# Touchstone.net
KiCad netlist of a schematic drawn in EAGLE
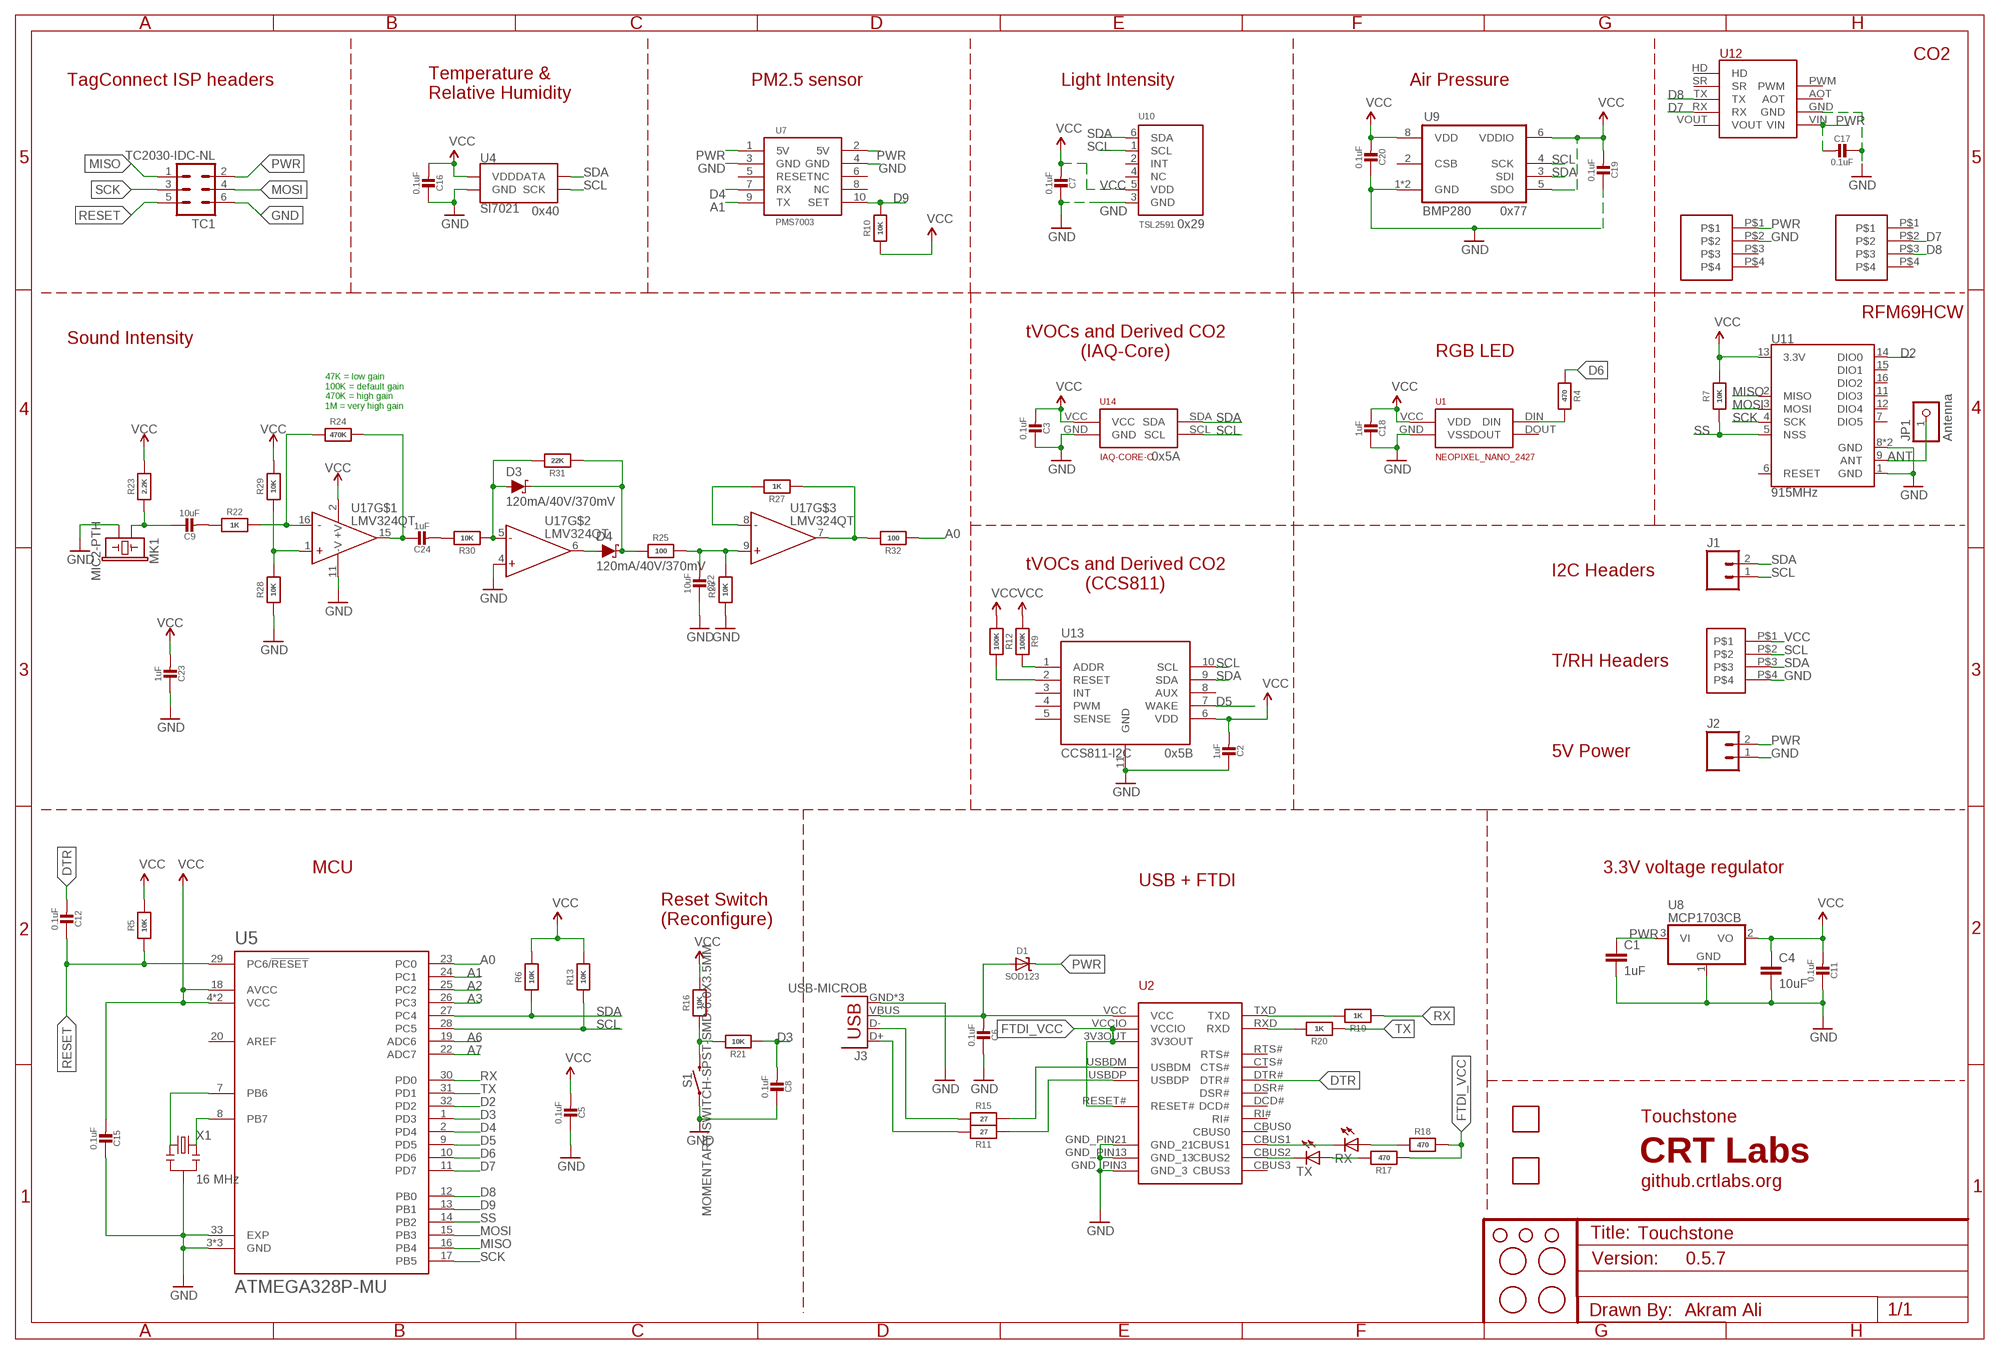
[diagram p0: schematic, sheet 1]

(export (version "E")
  (design (tool "Eeschema 10.0.6"))
  (components
    (comp (ref "C1")
      (value "1uF")
      (footprint "eagle-import:0805")
      (fields (field (name "MPN") "CC0805ZRY5V8BB105"))
      (libsource (lib "eagle-import") (part "CAP0805"))
    )
    (comp (ref "C2")
      (value "1uF")
      (footprint "eagle-import:MICROBUILDER__0402MP")
      (fields (field (name "MPN") "CC0402KRX5R6BB105"))
      (libsource (lib "eagle-import") (part "MICROBUILDER_CAP_CERAMIC_0402MP"))
    )
    (comp (ref "C3")
      (value "0.1uF")
      (footprint "eagle-import:MICROBUILDER__0402MP")
      (fields (field (name "MPN") "GRM155R71C104KA88J"))
      (libsource (lib "eagle-import") (part "MICROBUILDER_CAP_CERAMIC_0402MP"))
    )
    (comp (ref "C4")
      (value "10uF")
      (footprint "eagle-import:0805")
      (fields (field (name "MPN") "CC0805KKX5R6BB106"))
      (libsource (lib "eagle-import") (part "CAP0805"))
    )
    (comp (ref "C5")
      (value "0.1uF")
      (footprint "eagle-import:MICROBUILDER__0402MP")
      (fields (field (name "MPN") "GRM155R71C104KA88J"))
      (libsource (lib "eagle-import") (part "MICROBUILDER_CAP_CERAMIC_0402MP"))
    )
    (comp (ref "C6")
      (value "0.1uF")
      (footprint "eagle-import:MICROBUILDER__0402MP")
      (fields (field (name "MPN") "GRM155R71C104KA88J"))
      (libsource (lib "eagle-import") (part "MICROBUILDER_CAP_CERAMIC_0402MP"))
    )
    (comp (ref "C7")
      (value "0.1uF")
      (footprint "eagle-import:MICROBUILDER__0402MP")
      (fields (field (name "MPN") "GRM155R71C104KA88J"))
      (libsource (lib "eagle-import") (part "MICROBUILDER_CAP_CERAMIC_0402MP"))
    )
    (comp (ref "C8")
      (value "0.1uF")
      (footprint "eagle-import:MICROBUILDER__0402MP")
      (fields (field (name "MPN") "GRM155R71C104KA88J"))
      (libsource (lib "eagle-import") (part "MICROBUILDER_CAP_CERAMIC_0402MP"))
    )
    (comp (ref "C9")
      (value "10uF")
      (footprint "eagle-import:MICROBUILDER__0402MP")
      (fields (field (name "MPN") "GRJ155R60J106ME11D"))
      (libsource (lib "eagle-import") (part "MICROBUILDER_CAP_CERAMIC_0402MP"))
    )
    (comp (ref "C11")
      (value "0.1uF")
      (footprint "eagle-import:MICROBUILDER__0402MP")
      (fields (field (name "MPN") "GRM155R71C104KA88J"))
      (libsource (lib "eagle-import") (part "MICROBUILDER_CAP_CERAMIC_0402MP"))
    )
    (comp (ref "C12")
      (value "0.1uF")
      (footprint "eagle-import:MICROBUILDER__0402MP")
      (fields (field (name "MPN") "GRM155R71C104KA88J"))
      (libsource (lib "eagle-import") (part "MICROBUILDER_CAP_CERAMIC_0402MP"))
    )
    (comp (ref "C15")
      (value "0.1uF")
      (footprint "eagle-import:MICROBUILDER__0402MP")
      (fields (field (name "MPN") "GRM155R71C104KA88J"))
      (libsource (lib "eagle-import") (part "MICROBUILDER_CAP_CERAMIC_0402MP"))
    )
    (comp (ref "C16")
      (value "0.1uF")
      (footprint "eagle-import:MICROBUILDER__0402MP")
      (fields (field (name "MPN") "GRM155R71C104KA88J"))
      (libsource (lib "eagle-import") (part "MICROBUILDER_CAP_CERAMIC_0402MP"))
    )
    (comp (ref "C17")
      (value "0.1uF")
      (footprint "eagle-import:MICROBUILDER__0402MP")
      (fields (field (name "MPN") "GRM155R71C104KA88J"))
      (libsource (lib "eagle-import") (part "MICROBUILDER_CAP_CERAMIC_0402MP"))
    )
    (comp (ref "C18")
      (value "1uF")
      (footprint "eagle-import:MICROBUILDER__0402MP")
      (fields (field (name "MPN") "CC0402KRX5R6BB105"))
      (libsource (lib "eagle-import") (part "MICROBUILDER_CAP_CERAMIC_0402MP"))
    )
    (comp (ref "C19")
      (value "0.1uF")
      (footprint "eagle-import:MICROBUILDER__0402MP")
      (fields (field (name "MPN") "GRM155R71C104KA88J"))
      (libsource (lib "eagle-import") (part "MICROBUILDER_CAP_CERAMIC_0402MP"))
    )
    (comp (ref "C20")
      (value "0.1uF")
      (footprint "eagle-import:MICROBUILDER__0402MP")
      (fields (field (name "MPN") "GRM155R71C104KA88J"))
      (libsource (lib "eagle-import") (part "MICROBUILDER_CAP_CERAMIC_0402MP"))
    )
    (comp (ref "C22")
      (value "10uF")
      (footprint "eagle-import:MICROBUILDER__0402MP")
      (fields (field (name "MPN") "GRJ155R60J106ME11D"))
      (libsource (lib "eagle-import") (part "MICROBUILDER_CAP_CERAMIC_0402MP"))
    )
    (comp (ref "C23")
      (value "1uF")
      (footprint "eagle-import:MICROBUILDER__0402MP")
      (fields (field (name "MPN") "CC0402KRX5R6BB105"))
      (libsource (lib "eagle-import") (part "MICROBUILDER_CAP_CERAMIC_0402MP"))
    )
    (comp (ref "C24")
      (value "1uF")
      (footprint "eagle-import:MICROBUILDER__0402MP")
      (fields (field (name "MPN") "CC0402KRX5R6BB105"))
      (libsource (lib "eagle-import") (part "MICROBUILDER_CAP_CERAMIC_0402MP"))
    )
    (comp (ref "D1")
      (value "SOD123")
      (footprint "eagle-import:MICROBUILDER_SOD-123")
      (fields (field (name "MPN") "SD103AW-13-F"))
      (libsource (lib "eagle-import") (part "MICROBUILDER_DIODE-SCHOTTKYSOD-123"))
    )
    (comp (ref "D3")
      (value "120mA/40V/370mV")
      (footprint "eagle-import:SOD-523")
      (fields (field (name "MPN") "RB751S40T1G"))
      (libsource (lib "eagle-import") (part "DIODE-SCHOTTKY-RB751S40"))
    )
    (comp (ref "D4")
      (value "120mA/40V/370mV")
      (footprint "eagle-import:SOD-523")
      (fields (field (name "MPN") "RB751S40T1G"))
      (libsource (lib "eagle-import") (part "DIODE-SCHOTTKY-RB751S40"))
    )
    (comp (ref "H1")
      (value "STAND-OFF")
      (footprint "eagle-import:STAND-OFF")
      (libsource (lib "eagle-import") (part "STAND-OFF"))
    )
    (comp (ref "H2")
      (value "STAND-OFF")
      (footprint "eagle-import:STAND-OFF")
      (libsource (lib "eagle-import") (part "STAND-OFF"))
    )
    (comp (ref "H3")
      (value "STAND-OFF")
      (footprint "eagle-import:STAND-OFF")
      (libsource (lib "eagle-import") (part "STAND-OFF"))
    )
    (comp (ref "J1")
      (value "M02PTH")
      (footprint "eagle-import:1X02")
      (libsource (lib "eagle-import") (part "M02PTH"))
    )
    (comp (ref "J2")
      (value "M02PTH")
      (footprint "eagle-import:1X02")
      (libsource (lib "eagle-import") (part "M02PTH"))
    )
    (comp (ref "J3")
      (value "USB-MICROB")
      (footprint "eagle-import:USB-MICROB")
      (fields (field (name "MPN") "ZX62-B-5PA(33)"))
      (libsource (lib "eagle-import") (part "USB-MICROB"))
    )
    (comp (ref "JP1")
      (value "Antenna")
      (footprint "eagle-import:1X01-CLEANBIG")
      (fields (field (name "MPN") "Helical antenna"))
      (libsource (lib "eagle-import") (part "PINHD-1X1CB"))
    )
    (comp (ref "MK1")
      (value "MIC2-PTH")
      (footprint "eagle-import:MICROPHONE-PTH-4.0MM")
      (fields (field (name "MPN") "TOM-1545P-R"))
      (libsource (lib "eagle-import") (part "MIC2-PTH"))
    )
    (comp (ref "R4")
      (value "470")
      (footprint "eagle-import:MICROBUILDER__0402MP")
      (fields (field (name "MPN") "RC0402JR-07470RL"))
      (libsource (lib "eagle-import") (part "MICROBUILDER_RESISTOR_0402MP"))
    )
    (comp (ref "R5")
      (value "10K")
      (footprint "eagle-import:MICROBUILDER__0402MP")
      (fields (field (name "MPN") "RC0402JR-0710KL"))
      (libsource (lib "eagle-import") (part "MICROBUILDER_RESISTOR_0402MP"))
    )
    (comp (ref "R6")
      (value "10K")
      (footprint "eagle-import:MICROBUILDER__0402MP")
      (fields (field (name "MPN") "RC0402JR-0710KL"))
      (libsource (lib "eagle-import") (part "MICROBUILDER_RESISTOR_0402MP"))
    )
    (comp (ref "R7")
      (value "10K")
      (footprint "eagle-import:MICROBUILDER__0402MP")
      (fields (field (name "MPN") "RC0402JR-0710KL"))
      (libsource (lib "eagle-import") (part "MICROBUILDER_RESISTOR_0402MP"))
    )
    (comp (ref "R9")
      (value "100K")
      (footprint "eagle-import:MICROBUILDER__0402MP")
      (fields (field (name "MPN") "RC0402FR-07100KL"))
      (libsource (lib "eagle-import") (part "MICROBUILDER_RESISTOR_0402MP"))
    )
    (comp (ref "R10")
      (value "10K")
      (footprint "eagle-import:MICROBUILDER__0402MP")
      (fields (field (name "MPN") "RC0402JR-0710KL"))
      (libsource (lib "eagle-import") (part "MICROBUILDER_RESISTOR_0402MP"))
    )
    (comp (ref "R11")
      (value "27")
      (footprint "eagle-import:MICROBUILDER__0402MP")
      (fields (field (name "MPN") "RC0402JR-0727RL"))
      (libsource (lib "eagle-import") (part "MICROBUILDER_RESISTOR_0402MP"))
    )
    (comp (ref "R12")
      (value "100K")
      (footprint "eagle-import:MICROBUILDER__0402MP")
      (fields (field (name "MPN") "RC0402FR-07100KL"))
      (libsource (lib "eagle-import") (part "MICROBUILDER_RESISTOR_0402MP"))
    )
    (comp (ref "R13")
      (value "10K")
      (footprint "eagle-import:MICROBUILDER__0402MP")
      (fields (field (name "MPN") "RC0402JR-0710KL"))
      (libsource (lib "eagle-import") (part "MICROBUILDER_RESISTOR_0402MP"))
    )
    (comp (ref "R15")
      (value "27")
      (footprint "eagle-import:MICROBUILDER__0402MP")
      (fields (field (name "MPN") "RC0402JR-0727RL"))
      (libsource (lib "eagle-import") (part "MICROBUILDER_RESISTOR_0402MP"))
    )
    (comp (ref "R16")
      (value "10K")
      (footprint "eagle-import:MICROBUILDER__0402MP")
      (fields (field (name "MPN") "RC0402JR-0710KL"))
      (libsource (lib "eagle-import") (part "MICROBUILDER_RESISTOR_0402MP"))
    )
    (comp (ref "R17")
      (value "470")
      (footprint "eagle-import:MICROBUILDER__0402MP")
      (fields (field (name "MPN") "RC0402JR-07470RL"))
      (libsource (lib "eagle-import") (part "MICROBUILDER_RESISTOR_0402MP"))
    )
    (comp (ref "R18")
      (value "470")
      (footprint "eagle-import:MICROBUILDER__0402MP")
      (fields (field (name "MPN") "RC0402JR-07470RL"))
      (libsource (lib "eagle-import") (part "MICROBUILDER_RESISTOR_0402MP"))
    )
    (comp (ref "R19")
      (value "1K")
      (footprint "eagle-import:MICROBUILDER__0402MP")
      (fields (field (name "MPN") "RC0402JR-071KL"))
      (libsource (lib "eagle-import") (part "MICROBUILDER_RESISTOR_0402MP"))
    )
    (comp (ref "R20")
      (value "1K")
      (footprint "eagle-import:MICROBUILDER__0402MP")
      (fields (field (name "MPN") "RC0402JR-071KL"))
      (libsource (lib "eagle-import") (part "MICROBUILDER_RESISTOR_0402MP"))
    )
    (comp (ref "R21")
      (value "10K")
      (footprint "eagle-import:MICROBUILDER__0402MP")
      (fields (field (name "MPN") "RC0402JR-0710KL"))
      (libsource (lib "eagle-import") (part "MICROBUILDER_RESISTOR_0402MP"))
    )
    (comp (ref "R22")
      (value "1K")
      (footprint "eagle-import:MICROBUILDER__0402MP")
      (fields (field (name "MPN") "RC0402JR-071KL"))
      (libsource (lib "eagle-import") (part "Adafruit PowerBoost 1000C Rev B_MICROBUILDER_RESISTOR_0402MP"))
    )
    (comp (ref "R23")
      (value "2.2K")
      (footprint "eagle-import:MICROBUILDER__0402MP")
      (fields (field (name "MPN") "RC0402FR-072K2L"))
      (libsource (lib "eagle-import") (part "Adafruit PowerBoost 1000C Rev B_MICROBUILDER_RESISTOR_0402MP"))
    )
    (comp (ref "R24")
      (value "470K")
      (footprint "eagle-import:MICROBUILDER__0402MP")
      (fields (field (name "MPN") "RC0402FR-071ML"))
      (libsource (lib "eagle-import") (part "Adafruit PowerBoost 1000C Rev B_MICROBUILDER_RESISTOR_0402MP"))
    )
    (comp (ref "R25")
      (value "100")
      (footprint "eagle-import:MICROBUILDER__0402MP")
      (fields (field (name "MPN") "RC0402FR-07100RL"))
      (libsource (lib "eagle-import") (part "Adafruit PowerBoost 1000C Rev B_MICROBUILDER_RESISTOR_0402MP"))
    )
    (comp (ref "R26")
      (value "10K")
      (footprint "eagle-import:MICROBUILDER__0402MP")
      (fields (field (name "MPN") "RC0402JR-0710KL"))
      (libsource (lib "eagle-import") (part "Adafruit PowerBoost 1000C Rev B_MICROBUILDER_RESISTOR_0402MP"))
    )
    (comp (ref "R27")
      (value "1K")
      (footprint "eagle-import:MICROBUILDER__0402MP")
      (fields (field (name "MPN") "RC0402JR-071KL"))
      (libsource (lib "eagle-import") (part "Adafruit PowerBoost 1000C Rev B_MICROBUILDER_RESISTOR_0402MP"))
    )
    (comp (ref "R28")
      (value "10K")
      (footprint "eagle-import:MICROBUILDER__0402MP")
      (fields (field (name "MPN") "RC0402JR-0710KL"))
      (libsource (lib "eagle-import") (part "Adafruit PowerBoost 1000C Rev B_MICROBUILDER_RESISTOR_0402MP"))
    )
    (comp (ref "R29")
      (value "10K")
      (footprint "eagle-import:MICROBUILDER__0402MP")
      (fields (field (name "MPN") "RC0402JR-0710KL"))
      (libsource (lib "eagle-import") (part "Adafruit PowerBoost 1000C Rev B_MICROBUILDER_RESISTOR_0402MP"))
    )
    (comp (ref "R30")
      (value "10K")
      (footprint "eagle-import:MICROBUILDER__0402MP")
      (fields (field (name "MPN") "RC0402JR-0710KL"))
      (libsource (lib "eagle-import") (part "Adafruit PowerBoost 1000C Rev B_MICROBUILDER_RESISTOR_0402MP"))
    )
    (comp (ref "R31")
      (value "22K")
      (footprint "eagle-import:MICROBUILDER__0402MP")
      (fields (field (name "MPN") "RC0402JR-0722KL"))
      (libsource (lib "eagle-import") (part "Adafruit PowerBoost 1000C Rev B_MICROBUILDER_RESISTOR_0402MP"))
    )
    (comp (ref "R32")
      (value "100")
      (footprint "eagle-import:MICROBUILDER__0402MP")
      (fields (field (name "MPN") "RC0402FR-07100RL"))
      (libsource (lib "eagle-import") (part "Adafruit PowerBoost 1000C Rev B_MICROBUILDER_RESISTOR_0402MP"))
    )
    (comp (ref "RX")
      (value "LEDCHIPLED_0805")
      (footprint "eagle-import:CHIPLED_0805")
      (fields (field (name "MPN") "LG R971-KN-1"))
      (libsource (lib "eagle-import") (part "LEDCHIPLED_0805"))
    )
    (comp (ref "S1")
      (value "MOMENTARY-SWITCH-SPST-SMD-6.0X3.5MM")
      (footprint "eagle-import:TACTILE_SWITCH_SMD_6.0X3.5MM")
      (fields (field (name "MPN") "RS-032G05A3-SM RT"))
      (libsource (lib "eagle-import") (part "MOMENTARY-SWITCH-SPST-SMD-6.0X3.5MM"))
    )
    (comp (ref "TC1")
      (value "TC2030-IDC-NL")
      (footprint "eagle-import:TC2030-IDC-NL")
      (libsource (lib "eagle-import") (part "TC2030-IDC-NL"))
    )
    (comp (ref "TX")
      (value "LEDCHIPLED_0805")
      (footprint "eagle-import:CHIPLED_0805")
      (fields (field (name "MPN") "LG R971-KN-1"))
      (libsource (lib "eagle-import") (part "LEDCHIPLED_0805"))
    )
    (comp (ref "U$1")
      (value "FIDUCIAL")
      (footprint "eagle-import:FIDUCIAL_1MM")
      (libsource (lib "eagle-import") (part "FIDUCIAL"))
    )
    (comp (ref "U$2")
      (value "FIDUCIAL")
      (footprint "eagle-import:FIDUCIAL_1MM")
      (libsource (lib "eagle-import") (part "FIDUCIAL"))
    )
    (comp (ref "U$3")
      (value "FIDUCIAL")
      (footprint "eagle-import:FIDUCIAL_1MM")
      (libsource (lib "eagle-import") (part "FIDUCIAL"))
    )
    (comp (ref "U$4")
      (value "0878980426")
      (footprint "eagle-import:CONN_4POS_VERT_2.54_SMD")
      (libsource (lib "eagle-import") (part "0878980426"))
    )
    (comp (ref "U$5")
      (value "0878980426")
      (footprint "eagle-import:CONN_4POS_VERT_2.54_SMD")
      (libsource (lib "eagle-import") (part "0878980426"))
    )
    (comp (ref "U$6")
      (value "CONN_HDR_1.27MM_SMD_4POS")
      (footprint "eagle-import:CONN_HDR_1.27MM_SMD_4POS")
      (fields (field (name "MPN") "M50-3630442"))
      (libsource (lib "eagle-import") (part "CONN_HDR_1.27MM_SMD_4POS"))
    )
    (comp (ref "U$7")
      (value "FIDUCIAL")
      (footprint "eagle-import:FIDUCIAL_1MM")
      (libsource (lib "eagle-import") (part "FIDUCIAL"))
    )
    (comp (ref "U1")
      (value "NEOPIXEL_NANO_2427")
      (footprint "eagle-import:SK6805-2427")
      (fields (field (name "MPN") "3484"))
      (libsource (lib "eagle-import") (part "NEOPIXEL_NANO_2427"))
    )
    (comp (ref "U2")
      (value "FT231XQ-R")
      (footprint "eagle-import:FTDI_FT231XQ-R_PACKAGE")
      (libsource (lib "eagle-import") (part "FT231XQ-R"))
    )
    (comp (ref "U4")
      (value "SI7021")
      (footprint "eagle-import:DFN-6-3X3-SI7021")
      (fields (field (name "MPN") "SI7021-A20-GM1"))
      (libsource (lib "eagle-import") (part "SI7021"))
    )
    (comp (ref "U5")
      (value "ATMEGA328P-MU")
      (footprint "eagle-import:QFN50P500X500X100-33N")
      (fields (field (name "MF") "Atmel"))
      (libsource (lib "eagle-import") (part "ATMEGA328P-MU"))
    )
    (comp (ref "U7")
      (value "PMS7003")
      (footprint "eagle-import:PMS7003_RECEPTACLE_1.27MM_2X5")
      (fields (field (name "MPN") "20021311-00012T4LF"))
      (libsource (lib "eagle-import") (part "PMS7003"))
    )
    (comp (ref "U8")
      (value "MCP1703CB")
      (footprint "eagle-import:SOT23")
      (fields (field (name "MPN") "MCP1703T-3302E/CB"))
      (libsource (lib "eagle-import") (part "MCP1703CB"))
    )
    (comp (ref "U9")
      (value "BMP280")
      (footprint "eagle-import:BMP280")
      (libsource (lib "eagle-import") (part "BMP280"))
    )
    (comp (ref "U10")
      (value "TSL2591")
      (footprint "eagle-import:DFN6_TAOS")
      (fields (field (name "MPN") "TSL25911FN "))
      (libsource (lib "eagle-import") (part "LIGHT_TSL2591"))
    )
    (comp (ref "U11")
      (value "915MHz")
      (footprint "eagle-import:RFM69HCW-XXXS2")
      (fields (field (name "MPN") "RFM69HCW"))
      (libsource (lib "eagle-import") (part "RFM69HCW-915"))
    )
    (comp (ref "U12")
      (value "MH-Z19")
      (footprint "eagle-import:MH-Z19")
      (fields (field (name "MPN") "MH-z19"))
      (libsource (lib "eagle-import") (part "MH-Z19"))
    )
    (comp (ref "U13")
      (value "CCS811-I2C")
      (footprint "eagle-import:LGA")
      (fields (field (name "MPN") "CCS811"))
      (libsource (lib "eagle-import") (part "CCS811-I2C"))
    )
    (comp (ref "U14")
      (value "IAQ-CORE-C")
      (footprint "eagle-import:IAQ-CORE-C")
      (libsource (lib "eagle-import") (part "IAQ-CORE-C"))
    )
    (comp (ref "U15")
      (value "VLP-450-F")
      (footprint "eagle-import:VLP-450-F")
      (fields (field (name "MPN") "VLP-650-F"))
      (libsource (lib "eagle-import") (part "VLP-450-F"))
    )
    (comp (ref "U16")
      (value "VLP-450-F")
      (footprint "eagle-import:VLP-450-F")
      (fields (field (name "MPN") "VLP-550-F"))
      (libsource (lib "eagle-import") (part "VLP-450-F"))
    )
    (comp (ref "U17")
      (value "LMV324QT")
      (footprint "eagle-import:QFN-16_3X3")
      (fields (field (name "MPN") "LM324QT"))
      (libsource (lib "eagle-import") (part "LMV324QT"))
    )
    (comp (ref "X1")
      (value "16 MHz")
      (footprint "eagle-import:RESONATOR-SMD")
      (fields (field (name "MPN") "CSTCE16M0V53-R0"))
      (libsource (lib "eagle-import") (part "RESONATORSMD"))
    )
  )
  (nets
    (net (code "1") (name "/A0") (class "Default")
      (node (ref "R32") (pin "1") (pinfunction "1_1") (pintype "passive"))
      (node (ref "U5") (pin "23") (pinfunction "PC0_23") (pintype "bidirectional"))
    )
    (net (code "2") (name "/A1") (class "Default")
      (node (ref "U5") (pin "24") (pinfunction "PC1_24") (pintype "bidirectional"))
      (node (ref "U7") (pin "9") (pinfunction "TX_9") (pintype "bidirectional"))
    )
    (net (code "3") (name "/A2") (class "Default")
      (node (ref "U5") (pin "25") (pinfunction "PC2_25") (pintype "bidirectional"))
    )
    (net (code "4") (name "/A3") (class "Default")
      (node (ref "U5") (pin "26") (pinfunction "PC3_26") (pintype "bidirectional"))
    )
    (net (code "5") (name "/A6") (class "Default")
      (node (ref "U5") (pin "19") (pinfunction "ADC6_19") (pintype "bidirectional"))
    )
    (net (code "6") (name "/A7") (class "Default")
      (node (ref "U5") (pin "22") (pinfunction "ADC7_22") (pintype "bidirectional"))
    )
    (net (code "7") (name "/ANT") (class "Default")
      (node (ref "JP1") (pin "1") (pinfunction "1_1") (pintype "passive"))
      (node (ref "U11") (pin "9") (pinfunction "ANT_9") (pintype "passive"))
    )
    (net (code "8") (name "/D2") (class "Default")
      (node (ref "U11") (pin "14") (pinfunction "DIO0_14") (pintype "bidirectional"))
      (node (ref "U5") (pin "32") (pinfunction "PD2_32") (pintype "bidirectional"))
    )
    (net (code "9") (name "/D3") (class "Default")
      (node (ref "C8") (pin "2") (pinfunction "2_2") (pintype "passive"))
      (node (ref "R21") (pin "1") (pinfunction "1_1") (pintype "passive"))
      (node (ref "U5") (pin "1") (pinfunction "PD3_1") (pintype "bidirectional"))
    )
    (net (code "10") (name "/D4") (class "Default")
      (node (ref "U5") (pin "2") (pinfunction "PD4_2") (pintype "bidirectional"))
      (node (ref "U7") (pin "7") (pinfunction "RX_7") (pintype "bidirectional"))
    )
    (net (code "11") (name "/D5") (class "Default")
      (node (ref "U13") (pin "7") (pinfunction "WAKE_7") (pintype "bidirectional"))
      (node (ref "U5") (pin "9") (pinfunction "PD5_9") (pintype "bidirectional"))
    )
    (net (code "12") (name "/D7") (class "Default")
      (node (ref "U$5") (pin "P$2") (pinfunction "P$2_P$2") (pintype "bidirectional"))
      (node (ref "U12") (pin "RX") (pinfunction "RX_RX") (pintype "bidirectional"))
      (node (ref "U5") (pin "11") (pinfunction "PD7_11") (pintype "bidirectional"))
    )
    (net (code "13") (name "/D8") (class "Default")
      (node (ref "U$5") (pin "P$3") (pinfunction "P$3_P$3") (pintype "bidirectional"))
      (node (ref "U12") (pin "TX") (pinfunction "TX_TX") (pintype "bidirectional"))
      (node (ref "U5") (pin "12") (pinfunction "PB0_12") (pintype "bidirectional"))
    )
    (net (code "14") (name "/D9") (class "Default")
      (node (ref "R10") (pin "2") (pinfunction "2_2") (pintype "passive"))
      (node (ref "U5") (pin "13") (pinfunction "PB1_13") (pintype "bidirectional"))
      (node (ref "U7") (pin "10") (pinfunction "SET_10") (pintype "bidirectional"))
    )
    (net (code "15") (name "/SCL") (class "Default")
      (node (ref "J1") (pin "1") (pinfunction "1_1") (pintype "passive"))
      (node (ref "R13") (pin "1") (pinfunction "1_1") (pintype "passive"))
      (node (ref "U$6") (pin "P$2") (pinfunction "P$2_P$2") (pintype "bidirectional"))
      (node (ref "U10") (pin "1") (pinfunction "SCL_1") (pintype "bidirectional"))
      (node (ref "U13") (pin "10") (pinfunction "SCL_10") (pintype "bidirectional"))
      (node (ref "U14") (pin "SCL") (pinfunction "SCL_SCL") (pintype "bidirectional"))
      (node (ref "U4") (pin "SCK") (pinfunction "SCK_SCK") (pintype "input"))
      (node (ref "U5") (pin "28") (pinfunction "PC5_28") (pintype "bidirectional"))
      (node (ref "U9") (pin "4") (pinfunction "SCK_4") (pintype "bidirectional"))
    )
    (net (code "16") (name "/SDA") (class "Default")
      (node (ref "J1") (pin "2") (pinfunction "2_2") (pintype "passive"))
      (node (ref "R6") (pin "1") (pinfunction "1_1") (pintype "passive"))
      (node (ref "U$6") (pin "P$3") (pinfunction "P$3_P$3") (pintype "bidirectional"))
      (node (ref "U10") (pin "6") (pinfunction "SDA_6") (pintype "bidirectional"))
      (node (ref "U13") (pin "9") (pinfunction "SDA_9") (pintype "bidirectional"))
      (node (ref "U14") (pin "SDA") (pinfunction "SDA_SDA") (pintype "bidirectional"))
      (node (ref "U4") (pin "DATA") (pinfunction "DATA_DATA") (pintype "bidirectional"))
      (node (ref "U5") (pin "27") (pinfunction "PC4_27") (pintype "bidirectional"))
      (node (ref "U9") (pin "3") (pinfunction "SDI_3") (pintype "bidirectional"))
    )
    (net (code "17") (name "/SS") (class "Default")
      (node (ref "R7") (pin "1") (pinfunction "1_1") (pintype "passive"))
      (node (ref "U11") (pin "5") (pinfunction "NSS_5") (pintype "input"))
      (node (ref "U5") (pin "14") (pinfunction "PB2_14") (pintype "bidirectional"))
    )
    (net (code "18") (name "D6") (class "Default")
      (node (ref "R4") (pin "1") (pinfunction "1_1") (pintype "passive"))
      (node (ref "U5") (pin "10") (pinfunction "PD6_10") (pintype "bidirectional"))
    )
    (net (code "19") (name "DTR") (class "Default")
      (node (ref "C12") (pin "2") (pinfunction "2_2") (pintype "passive"))
      (node (ref "U2") (pin "DTR#") (pinfunction "DTR#_DTR#") (pintype "bidirectional"))
    )
    (net (code "20") (name "FTDI_VCC") (class "Default")
      (node (ref "R17") (pin "1") (pinfunction "1_1") (pintype "passive"))
      (node (ref "R18") (pin "2") (pinfunction "2_2") (pintype "passive"))
      (node (ref "U2") (pin "3V3OUT") (pinfunction "3V3OUT_3V3OUT") (pintype "bidirectional"))
      (node (ref "U2") (pin "RESET#") (pinfunction "RESET#_RESET#") (pintype "bidirectional"))
      (node (ref "U2") (pin "VCCIO") (pinfunction "VCCIO_VCCIO") (pintype "bidirectional"))
    )
    (net (code "21") (name "GND") (class "Default")
      (node (ref "C1") (pin "2") (pinfunction "2_2") (pintype "passive"))
      (node (ref "C11") (pin "1") (pinfunction "1_1") (pintype "passive"))
      (node (ref "C15") (pin "1") (pinfunction "1_1") (pintype "passive"))
      (node (ref "C16") (pin "1") (pinfunction "1_1") (pintype "passive"))
      (node (ref "C17") (pin "1") (pinfunction "1_1") (pintype "passive"))
      (node (ref "C18") (pin "1") (pinfunction "1_1") (pintype "passive"))
      (node (ref "C19") (pin "1") (pinfunction "1_1") (pintype "passive"))
      (node (ref "C2") (pin "1") (pinfunction "1_1") (pintype "passive"))
      (node (ref "C20") (pin "1") (pinfunction "1_1") (pintype "passive"))
      (node (ref "C22") (pin "1") (pinfunction "1_1") (pintype "passive"))
      (node (ref "C23") (pin "1") (pinfunction "1_1") (pintype "passive"))
      (node (ref "C3") (pin "1") (pinfunction "1_1") (pintype "passive"))
      (node (ref "C4") (pin "2") (pinfunction "2_2") (pintype "passive"))
      (node (ref "C5") (pin "1") (pinfunction "1_1") (pintype "passive"))
      (node (ref "C6") (pin "1") (pinfunction "1_1") (pintype "passive"))
      (node (ref "C7") (pin "1") (pinfunction "1_1") (pintype "passive"))
      (node (ref "C8") (pin "1") (pinfunction "1_1") (pintype "passive"))
      (node (ref "J2") (pin "1") (pinfunction "1_1") (pintype "passive"))
      (node (ref "J3") (pin "GND") (pinfunction "GND_GND") (pintype "bidirectional"))
      (node (ref "J3") (pin "MT1") (pinfunction "GND_MT1") (pintype "bidirectional"))
      (node (ref "J3") (pin "MT2") (pinfunction "GND_MT2") (pintype "bidirectional"))
      (node (ref "MK1") (pin "GND") (pinfunction "2_GND") (pintype "passive"))
      (node (ref "R26") (pin "1") (pinfunction "1_1") (pintype "passive"))
      (node (ref "R28") (pin "1") (pinfunction "1_1") (pintype "passive"))
      (node (ref "S1") (pin "1") (pinfunction "1_1") (pintype "passive"))
      (node (ref "TC1") (pin "6") (pinfunction "6_6") (pintype "passive"))
      (node (ref "U$4") (pin "P$2") (pinfunction "P$2_P$2") (pintype "bidirectional"))
      (node (ref "U$6") (pin "P$4") (pinfunction "P$4_P$4") (pintype "bidirectional"))
      (node (ref "U1") (pin "GND") (pinfunction "VSS_GND") (pintype "bidirectional"))
      (node (ref "U10") (pin "3") (pinfunction "GND_3") (pintype "power_in"))
      (node (ref "U11") (pin "1") (pinfunction "GND_1") (pintype "power_in"))
      (node (ref "U11") (pin "10") (pinfunction "GND_10") (pintype "power_in"))
      (node (ref "U11") (pin "8") (pinfunction "GND_8") (pintype "power_in"))
      (node (ref "U12") (pin "GND") (pinfunction "GND_GND") (pintype "bidirectional"))
      (node (ref "U13") (pin "11") (pinfunction "GND_11") (pintype "bidirectional"))
      (node (ref "U14") (pin "GND") (pinfunction "GND_GND") (pintype "bidirectional"))
      (node (ref "U17") (pin "11") (pinfunction "-V_11") (pintype "power_in"))
      (node (ref "U17") (pin "4") (pinfunction "+IN_4") (pintype "input"))
      (node (ref "U2") (pin "GND_PIN13") (pinfunction "GND_13_GND_PIN13") (pintype "bidirectional"))
      (node (ref "U2") (pin "GND_PIN21") (pinfunction "GND_21_GND_PIN21") (pintype "bidirectional"))
      (node (ref "U2") (pin "GND_PIN3") (pinfunction "GND_3_GND_PIN3") (pintype "bidirectional"))
      (node (ref "U4") (pin "GND") (pinfunction "GND_GND") (pintype "power_in"))
      (node (ref "U5") (pin "21") (pinfunction "GND_21") (pintype "power_in"))
      (node (ref "U5") (pin "3") (pinfunction "GND_3") (pintype "power_in"))
      (node (ref "U5") (pin "33") (pinfunction "EXP_33") (pintype "power_in"))
      (node (ref "U5") (pin "5") (pinfunction "GND_5") (pintype "power_in"))
      (node (ref "U7") (pin "3") (pinfunction "GND_3") (pintype "bidirectional"))
      (node (ref "U7") (pin "4") (pinfunction "GND_4") (pintype "bidirectional"))
      (node (ref "U8") (pin "1") (pinfunction "GND_1") (pintype "passive"))
      (node (ref "U9") (pin "1") (pinfunction "GND_1") (pintype "power_in"))
      (node (ref "U9") (pin "7") (pinfunction "GND_7") (pintype "power_in"))
      (node (ref "X1") (pin "2") (pinfunction "2_2") (pintype "passive"))
    )
    (net (code "22") (name "MISO") (class "Default")
      (node (ref "TC1") (pin "1") (pinfunction "1_1") (pintype "passive"))
      (node (ref "U11") (pin "2") (pinfunction "MISO_2") (pintype "bidirectional"))
      (node (ref "U5") (pin "16") (pinfunction "PB4_16") (pintype "bidirectional"))
    )
    (net (code "23") (name "MOSI") (class "Default")
      (node (ref "TC1") (pin "4") (pinfunction "4_4") (pintype "passive"))
      (node (ref "U11") (pin "3") (pinfunction "MOSI_3") (pintype "input"))
      (node (ref "U5") (pin "15") (pinfunction "PB3_15") (pintype "bidirectional"))
    )
    (net (code "24") (name "Net-(C6-Pad2)") (class "Default")
      (node (ref "C6") (pin "2") (pinfunction "2_2") (pintype "passive"))
      (node (ref "D1") (pin "A") (pinfunction "A_A") (pintype "passive"))
      (node (ref "J3") (pin "VBUS") (pinfunction "VBUS_VBUS") (pintype "bidirectional"))
      (node (ref "U2") (pin "VCC") (pinfunction "VCC_VCC") (pintype "bidirectional"))
    )
    (net (code "25") (name "Net-(C9-Pad2)") (class "Default")
      (node (ref "C9") (pin "2") (pinfunction "2_2") (pintype "passive"))
      (node (ref "R22") (pin "1") (pinfunction "1_1") (pintype "passive"))
    )
    (net (code "26") (name "Net-(C24-Pad2)") (class "Default")
      (node (ref "C24") (pin "2") (pinfunction "2_2") (pintype "passive"))
      (node (ref "R30") (pin "2") (pinfunction "2_2") (pintype "passive"))
    )
    (net (code "27") (name "Net-(D3-PadC)") (class "Default")
      (node (ref "D3") (pin "C") (pinfunction "C_C") (pintype "passive"))
      (node (ref "D4") (pin "C") (pinfunction "C_C") (pintype "passive"))
      (node (ref "R25") (pin "1") (pinfunction "1_1") (pintype "passive"))
      (node (ref "R31") (pin "1") (pinfunction "1_1") (pintype "passive"))
    )
    (net (code "28") (name "Net-(J3-PadD+)") (class "Default")
      (node (ref "J3") (pin "D+") (pinfunction "D+_D+") (pintype "bidirectional"))
      (node (ref "R11") (pin "2") (pinfunction "2_2") (pintype "passive"))
    )
    (net (code "29") (name "Net-(J3-PadD-)") (class "Default")
      (node (ref "J3") (pin "D-") (pinfunction "D-_D-") (pintype "bidirectional"))
      (node (ref "R15") (pin "1") (pinfunction "1_1") (pintype "passive"))
    )
    (net (code "30") (name "Net-(MK1-1)") (class "Default")
      (node (ref "C9") (pin "1") (pinfunction "1_1") (pintype "passive"))
      (node (ref "MK1") (pin "OUT") (pinfunction "1_OUT") (pintype "passive"))
      (node (ref "R23") (pin "1") (pinfunction "1_1") (pintype "passive"))
    )
    (net (code "31") (name "Net-(R4-Pad2)") (class "Default")
      (node (ref "R4") (pin "2") (pinfunction "2_2") (pintype "passive"))
      (node (ref "U1") (pin "DIN") (pinfunction "DIN_DIN") (pintype "bidirectional"))
    )
    (net (code "32") (name "Net-(R11-Pad1)") (class "Default")
      (node (ref "R11") (pin "1") (pinfunction "1_1") (pintype "passive"))
      (node (ref "U2") (pin "USBDP") (pinfunction "USBDP_USBDP") (pintype "bidirectional"))
    )
    (net (code "33") (name "Net-(R15-Pad2)") (class "Default")
      (node (ref "R15") (pin "2") (pinfunction "2_2") (pintype "passive"))
      (node (ref "U2") (pin "USBDM") (pinfunction "USBDM_USBDM") (pintype "bidirectional"))
    )
    (net (code "34") (name "Net-(R16-Pad1)") (class "Default")
      (node (ref "R16") (pin "1") (pinfunction "1_1") (pintype "passive"))
      (node (ref "R21") (pin "2") (pinfunction "2_2") (pintype "passive"))
      (node (ref "S1") (pin "2") (pinfunction "2_2") (pintype "passive"))
    )
    (net (code "35") (name "Net-(R17-Pad2)") (class "Default")
      (node (ref "R17") (pin "2") (pinfunction "2_2") (pintype "passive"))
      (node (ref "TX") (pin "A") (pinfunction "A_A") (pintype "passive"))
    )
    (net (code "36") (name "Net-(R18-Pad1)") (class "Default")
      (node (ref "R18") (pin "1") (pinfunction "1_1") (pintype "passive"))
      (node (ref "RX") (pin "A") (pinfunction "A_A") (pintype "passive"))
    )
    (net (code "37") (name "Net-(R19-Pad2)") (class "Default")
      (node (ref "R19") (pin "2") (pinfunction "2_2") (pintype "passive"))
      (node (ref "U2") (pin "TXD") (pinfunction "TXD_TXD") (pintype "bidirectional"))
    )
    (net (code "38") (name "Net-(R20-Pad2)") (class "Default")
      (node (ref "R20") (pin "2") (pinfunction "2_2") (pintype "passive"))
      (node (ref "U2") (pin "RXD") (pinfunction "RXD_RXD") (pintype "bidirectional"))
    )
    (net (code "39") (name "Net-(RX-PadC)") (class "Default")
      (node (ref "RX") (pin "C") (pinfunction "C_C") (pintype "passive"))
      (node (ref "U2") (pin "CBUS1") (pinfunction "CBUS1_CBUS1") (pintype "bidirectional"))
    )
    (net (code "40") (name "Net-(TX-PadC)") (class "Default")
      (node (ref "TX") (pin "C") (pinfunction "C_C") (pintype "passive"))
      (node (ref "U2") (pin "CBUS2") (pinfunction "CBUS2_CBUS2") (pintype "bidirectional"))
    )
    (net (code "41") (name "Net-(U5-PB6)") (class "Default")
      (node (ref "U5") (pin "7") (pinfunction "PB6_7") (pintype "bidirectional"))
      (node (ref "X1") (pin "1") (pinfunction "1_1") (pintype "passive"))
    )
    (net (code "42") (name "Net-(U5-PB7)") (class "Default")
      (node (ref "U5") (pin "8") (pinfunction "PB7_8") (pintype "bidirectional"))
      (node (ref "X1") (pin "3") (pinfunction "3_3") (pintype "passive"))
    )
    (net (code "43") (name "Net-(U13-ADDR)") (class "Default")
      (node (ref "R9") (pin "2") (pinfunction "2_2") (pintype "passive"))
      (node (ref "U13") (pin "1") (pinfunction "ADDR_1") (pintype "bidirectional"))
    )
    (net (code "44") (name "Net-(U13-RESET)") (class "Default")
      (node (ref "R12") (pin "2") (pinfunction "2_2") (pintype "passive"))
      (node (ref "U13") (pin "2") (pinfunction "RESET_2") (pintype "bidirectional"))
    )
    (net (code "45") (name "Net-(U17A-+IN)") (class "Default")
      (node (ref "R28") (pin "2") (pinfunction "2_2") (pintype "passive"))
      (node (ref "R29") (pin "1") (pinfunction "1_1") (pintype "passive"))
      (node (ref "U17") (pin "1") (pinfunction "+IN_1") (pintype "input"))
    )
    (net (code "46") (name "Net-(U17A--IN)") (class "Default")
      (node (ref "R22") (pin "2") (pinfunction "2_2") (pintype "passive"))
      (node (ref "R24") (pin "1") (pinfunction "1_1") (pintype "passive"))
      (node (ref "U17") (pin "16") (pinfunction "-IN_16") (pintype "input"))
    )
    (net (code "47") (name "Net-(U17A-OUT)") (class "Default")
      (node (ref "C24") (pin "1") (pinfunction "1_1") (pintype "passive"))
      (node (ref "R24") (pin "2") (pinfunction "2_2") (pintype "passive"))
      (node (ref "U17") (pin "15") (pinfunction "OUT_15") (pintype "output"))
    )
    (net (code "48") (name "Net-(U17B--IN)") (class "Default")
      (node (ref "D3") (pin "A") (pinfunction "A_A") (pintype "passive"))
      (node (ref "R30") (pin "1") (pinfunction "1_1") (pintype "passive"))
      (node (ref "R31") (pin "2") (pinfunction "2_2") (pintype "passive"))
      (node (ref "U17") (pin "5") (pinfunction "-IN_5") (pintype "input"))
    )
    (net (code "49") (name "Net-(U17B-OUT)") (class "Default")
      (node (ref "D4") (pin "A") (pinfunction "A_A") (pintype "passive"))
      (node (ref "U17") (pin "6") (pinfunction "OUT_6") (pintype "output"))
    )
    (net (code "50") (name "Net-(U17C-+IN)") (class "Default")
      (node (ref "C22") (pin "2") (pinfunction "2_2") (pintype "passive"))
      (node (ref "R25") (pin "2") (pinfunction "2_2") (pintype "passive"))
      (node (ref "R26") (pin "2") (pinfunction "2_2") (pintype "passive"))
      (node (ref "U17") (pin "9") (pinfunction "+IN_9") (pintype "input"))
    )
    (net (code "51") (name "Net-(U17C--IN)") (class "Default")
      (node (ref "R27") (pin "2") (pinfunction "2_2") (pintype "passive"))
      (node (ref "U17") (pin "8") (pinfunction "-IN_8") (pintype "input"))
    )
    (net (code "52") (name "Net-(U17C-OUT)") (class "Default")
      (node (ref "R27") (pin "1") (pinfunction "1_1") (pintype "passive"))
      (node (ref "R32") (pin "2") (pinfunction "2_2") (pintype "passive"))
      (node (ref "U17") (pin "7") (pinfunction "OUT_7") (pintype "output"))
    )
    (net (code "53") (name "PWR") (class "Default")
      (node (ref "C1") (pin "1") (pinfunction "1_1") (pintype "passive"))
      (node (ref "C17") (pin "2") (pinfunction "2_2") (pintype "passive"))
      (node (ref "D1") (pin "C") (pinfunction "C_C") (pintype "passive"))
      (node (ref "J2") (pin "2") (pinfunction "2_2") (pintype "passive"))
      (node (ref "TC1") (pin "2") (pinfunction "2_2") (pintype "passive"))
      (node (ref "U$4") (pin "P$1") (pinfunction "P$1_P$1") (pintype "bidirectional"))
      (node (ref "U12") (pin "VIN") (pinfunction "VIN_VIN") (pintype "bidirectional"))
      (node (ref "U7") (pin "1") (pinfunction "5V_1") (pintype "bidirectional"))
      (node (ref "U7") (pin "2") (pinfunction "5V_2") (pintype "bidirectional"))
      (node (ref "U8") (pin "3") (pinfunction "VI_3") (pintype "input"))
    )
    (net (code "54") (name "RESET") (class "Default")
      (node (ref "C12") (pin "1") (pinfunction "1_1") (pintype "passive"))
      (node (ref "R5") (pin "1") (pinfunction "1_1") (pintype "passive"))
      (node (ref "TC1") (pin "5") (pinfunction "5_5") (pintype "passive"))
      (node (ref "U5") (pin "29") (pinfunction "PC6/~{RESET}_29") (pintype "bidirectional"))
    )
    (net (code "55") (name "RX") (class "Default")
      (node (ref "R19") (pin "1") (pinfunction "1_1") (pintype "passive"))
      (node (ref "U5") (pin "30") (pinfunction "PD0_30") (pintype "bidirectional"))
    )
    (net (code "56") (name "SCK") (class "Default")
      (node (ref "TC1") (pin "3") (pinfunction "3_3") (pintype "passive"))
      (node (ref "U11") (pin "4") (pinfunction "SCK_4") (pintype "input"))
      (node (ref "U5") (pin "17") (pinfunction "PB5_17") (pintype "bidirectional"))
    )
    (net (code "57") (name "TX") (class "Default")
      (node (ref "R20") (pin "1") (pinfunction "1_1") (pintype "passive"))
      (node (ref "U5") (pin "31") (pinfunction "PD1_31") (pintype "bidirectional"))
    )
    (net (code "58") (name "VCC") (class "Default")
      (node (ref "C11") (pin "2") (pinfunction "2_2") (pintype "passive"))
      (node (ref "C15") (pin "2") (pinfunction "2_2") (pintype "passive"))
      (node (ref "C16") (pin "2") (pinfunction "2_2") (pintype "passive"))
      (node (ref "C18") (pin "2") (pinfunction "2_2") (pintype "passive"))
      (node (ref "C19") (pin "2") (pinfunction "2_2") (pintype "passive"))
      (node (ref "C2") (pin "2") (pinfunction "2_2") (pintype "passive"))
      (node (ref "C20") (pin "2") (pinfunction "2_2") (pintype "passive"))
      (node (ref "C23") (pin "2") (pinfunction "2_2") (pintype "passive"))
      (node (ref "C3") (pin "2") (pinfunction "2_2") (pintype "passive"))
      (node (ref "C4") (pin "1") (pinfunction "1_1") (pintype "passive"))
      (node (ref "C5") (pin "2") (pinfunction "2_2") (pintype "passive"))
      (node (ref "C7") (pin "2") (pinfunction "2_2") (pintype "passive"))
      (node (ref "R10") (pin "1") (pinfunction "1_1") (pintype "passive"))
      (node (ref "R12") (pin "1") (pinfunction "1_1") (pintype "passive"))
      (node (ref "R13") (pin "2") (pinfunction "2_2") (pintype "passive"))
      (node (ref "R16") (pin "2") (pinfunction "2_2") (pintype "passive"))
      (node (ref "R23") (pin "2") (pinfunction "2_2") (pintype "passive"))
      (node (ref "R29") (pin "2") (pinfunction "2_2") (pintype "passive"))
      (node (ref "R5") (pin "2") (pinfunction "2_2") (pintype "passive"))
      (node (ref "R6") (pin "2") (pinfunction "2_2") (pintype "passive"))
      (node (ref "R7") (pin "2") (pinfunction "2_2") (pintype "passive"))
      (node (ref "R9") (pin "1") (pinfunction "1_1") (pintype "passive"))
      (node (ref "U$6") (pin "P$1") (pinfunction "P$1_P$1") (pintype "bidirectional"))
      (node (ref "U1") (pin "VCC") (pinfunction "VDD_VCC") (pintype "bidirectional"))
      (node (ref "U10") (pin "5") (pinfunction "VDD_5") (pintype "power_in"))
      (node (ref "U11") (pin "13") (pinfunction "3.3V_13") (pintype "power_in"))
      (node (ref "U13") (pin "6") (pinfunction "VDD_6") (pintype "bidirectional"))
      (node (ref "U14") (pin "VCC") (pinfunction "VCC_VCC") (pintype "bidirectional"))
      (node (ref "U17") (pin "2") (pinfunction "+V_2") (pintype "power_in"))
      (node (ref "U4") (pin "VDD") (pinfunction "VDD_VDD") (pintype "power_in"))
      (node (ref "U5") (pin "18") (pinfunction "AVCC_18") (pintype "power_in"))
      (node (ref "U5") (pin "4") (pinfunction "VCC_4") (pintype "power_in"))
      (node (ref "U5") (pin "6") (pinfunction "VCC_6") (pintype "power_in"))
      (node (ref "U8") (pin "2") (pinfunction "VO_2") (pintype "passive"))
      (node (ref "U9") (pin "5") (pinfunction "SDO_5") (pintype "input"))
      (node (ref "U9") (pin "6") (pinfunction "VDDIO_6") (pintype "power_in"))
      (node (ref "U9") (pin "8") (pinfunction "VDD_8") (pintype "power_in"))
    )
    (net (code "59") (name "unconnected-(U$4-PadP$3)") (class "Default")
      (node (ref "U$4") (pin "P$3") (pinfunction "P$3_P$3") (pintype "bidirectional"))
    )
    (net (code "60") (name "unconnected-(U$4-PadP$4)") (class "Default")
      (node (ref "U$4") (pin "P$4") (pinfunction "P$4_P$4") (pintype "bidirectional"))
    )
    (net (code "61") (name "unconnected-(U$5-PadP$1)") (class "Default")
      (node (ref "U$5") (pin "P$1") (pinfunction "P$1_P$1") (pintype "bidirectional"))
    )
    (net (code "62") (name "unconnected-(U$5-PadP$4)") (class "Default")
      (node (ref "U$5") (pin "P$4") (pinfunction "P$4_P$4") (pintype "bidirectional"))
    )
    (net (code "63") (name "unconnected-(U1-PadDOUT)") (class "Default")
      (node (ref "U1") (pin "DOUT") (pinfunction "DOUT_DOUT") (pintype "bidirectional"))
    )
    (net (code "64") (name "unconnected-(U2-PadCBUS0)") (class "Default")
      (node (ref "U2") (pin "CBUS0") (pinfunction "CBUS0_CBUS0") (pintype "bidirectional"))
    )
    (net (code "65") (name "unconnected-(U2-PadCBUS3)") (class "Default")
      (node (ref "U2") (pin "CBUS3") (pinfunction "CBUS3_CBUS3") (pintype "bidirectional"))
    )
    (net (code "66") (name "unconnected-(U2-PadCTS#)") (class "Default")
      (node (ref "U2") (pin "CTS#") (pinfunction "CTS#_CTS#") (pintype "bidirectional"))
    )
    (net (code "67") (name "unconnected-(U2-PadDCD#)") (class "Default")
      (node (ref "U2") (pin "DCD#") (pinfunction "DCD#_DCD#") (pintype "bidirectional"))
    )
    (net (code "68") (name "unconnected-(U2-PadDSR#)") (class "Default")
      (node (ref "U2") (pin "DSR#") (pinfunction "DSR#_DSR#") (pintype "bidirectional"))
    )
    (net (code "69") (name "unconnected-(U2-PadRI#)") (class "Default")
      (node (ref "U2") (pin "RI#") (pinfunction "RI#_RI#") (pintype "bidirectional"))
    )
    (net (code "70") (name "unconnected-(U2-PadRTS#)") (class "Default")
      (node (ref "U2") (pin "RTS#") (pinfunction "RTS#_RTS#") (pintype "bidirectional"))
    )
    (net (code "71") (name "unconnected-(U5-AREF-Pad20)") (class "Default")
      (node (ref "U5") (pin "20") (pinfunction "AREF_20") (pintype "input"))
    )
    (net (code "72") (name "unconnected-(U7-NC-Pad6)") (class "Default")
      (node (ref "U7") (pin "6") (pinfunction "NC_6") (pintype "bidirectional"))
    )
    (net (code "73") (name "unconnected-(U7-NC-Pad8)") (class "Default")
      (node (ref "U7") (pin "8") (pinfunction "NC_8") (pintype "bidirectional"))
    )
    (net (code "74") (name "unconnected-(U7-RESET-Pad5)") (class "Default")
      (node (ref "U7") (pin "5") (pinfunction "RESET_5") (pintype "bidirectional"))
    )
    (net (code "75") (name "unconnected-(U9-CSB-Pad2)") (class "Default")
      (node (ref "U9") (pin "2") (pinfunction "CSB_2") (pintype "input"))
    )
    (net (code "76") (name "unconnected-(U10-INT-Pad2)") (class "Default")
      (node (ref "U10") (pin "2") (pinfunction "INT_2") (pintype "output"))
    )
    (net (code "77") (name "unconnected-(U10-NC-Pad4)") (class "Default")
      (node (ref "U10") (pin "4") (pinfunction "NC_4") (pintype "no_connect"))
    )
    (net (code "78") (name "unconnected-(U11-DIO1-Pad15)") (class "Default")
      (node (ref "U11") (pin "15") (pinfunction "DIO1_15") (pintype "bidirectional"))
    )
    (net (code "79") (name "unconnected-(U11-DIO2-Pad16)") (class "Default")
      (node (ref "U11") (pin "16") (pinfunction "DIO2_16") (pintype "bidirectional"))
    )
    (net (code "80") (name "unconnected-(U11-DIO3-Pad11)") (class "Default")
      (node (ref "U11") (pin "11") (pinfunction "DIO3_11") (pintype "bidirectional"))
    )
    (net (code "81") (name "unconnected-(U11-DIO4-Pad12)") (class "Default")
      (node (ref "U11") (pin "12") (pinfunction "DIO4_12") (pintype "bidirectional"))
    )
    (net (code "82") (name "unconnected-(U11-DIO5-Pad7)") (class "Default")
      (node (ref "U11") (pin "7") (pinfunction "DIO5_7") (pintype "bidirectional"))
    )
    (net (code "83") (name "unconnected-(U11-RESET-Pad6)") (class "Default")
      (node (ref "U11") (pin "6") (pinfunction "RESET_6") (pintype "input"))
    )
    (net (code "84") (name "unconnected-(U12-PadAOT)") (class "Default")
      (node (ref "U12") (pin "AOT") (pinfunction "AOT_AOT") (pintype "bidirectional"))
    )
    (net (code "85") (name "unconnected-(U12-PadHD)") (class "Default")
      (node (ref "U12") (pin "HD") (pinfunction "HD_HD") (pintype "bidirectional"))
    )
    (net (code "86") (name "unconnected-(U12-PadPWM)") (class "Default")
      (node (ref "U12") (pin "PWM") (pinfunction "PWM_PWM") (pintype "bidirectional"))
    )
    (net (code "87") (name "unconnected-(U12-PadSR)") (class "Default")
      (node (ref "U12") (pin "SR") (pinfunction "SR_SR") (pintype "bidirectional"))
    )
    (net (code "88") (name "unconnected-(U12-PadVOUT)") (class "Default")
      (node (ref "U12") (pin "VOUT") (pinfunction "VOUT_VOUT") (pintype "bidirectional"))
    )
    (net (code "89") (name "unconnected-(U13-AUX-Pad8)") (class "Default")
      (node (ref "U13") (pin "8") (pinfunction "AUX_8") (pintype "bidirectional"))
    )
    (net (code "90") (name "unconnected-(U13-INT-Pad3)") (class "Default")
      (node (ref "U13") (pin "3") (pinfunction "INT_3") (pintype "bidirectional"))
    )
    (net (code "91") (name "unconnected-(U13-PWM-Pad4)") (class "Default")
      (node (ref "U13") (pin "4") (pinfunction "PWM_4") (pintype "bidirectional"))
    )
    (net (code "92") (name "unconnected-(U13-SENSE-Pad5)") (class "Default")
      (node (ref "U13") (pin "5") (pinfunction "SENSE_5") (pintype "bidirectional"))
    )
  )
)
